# pimc.net
KiCad netlist of a schematic drawn in EAGLE
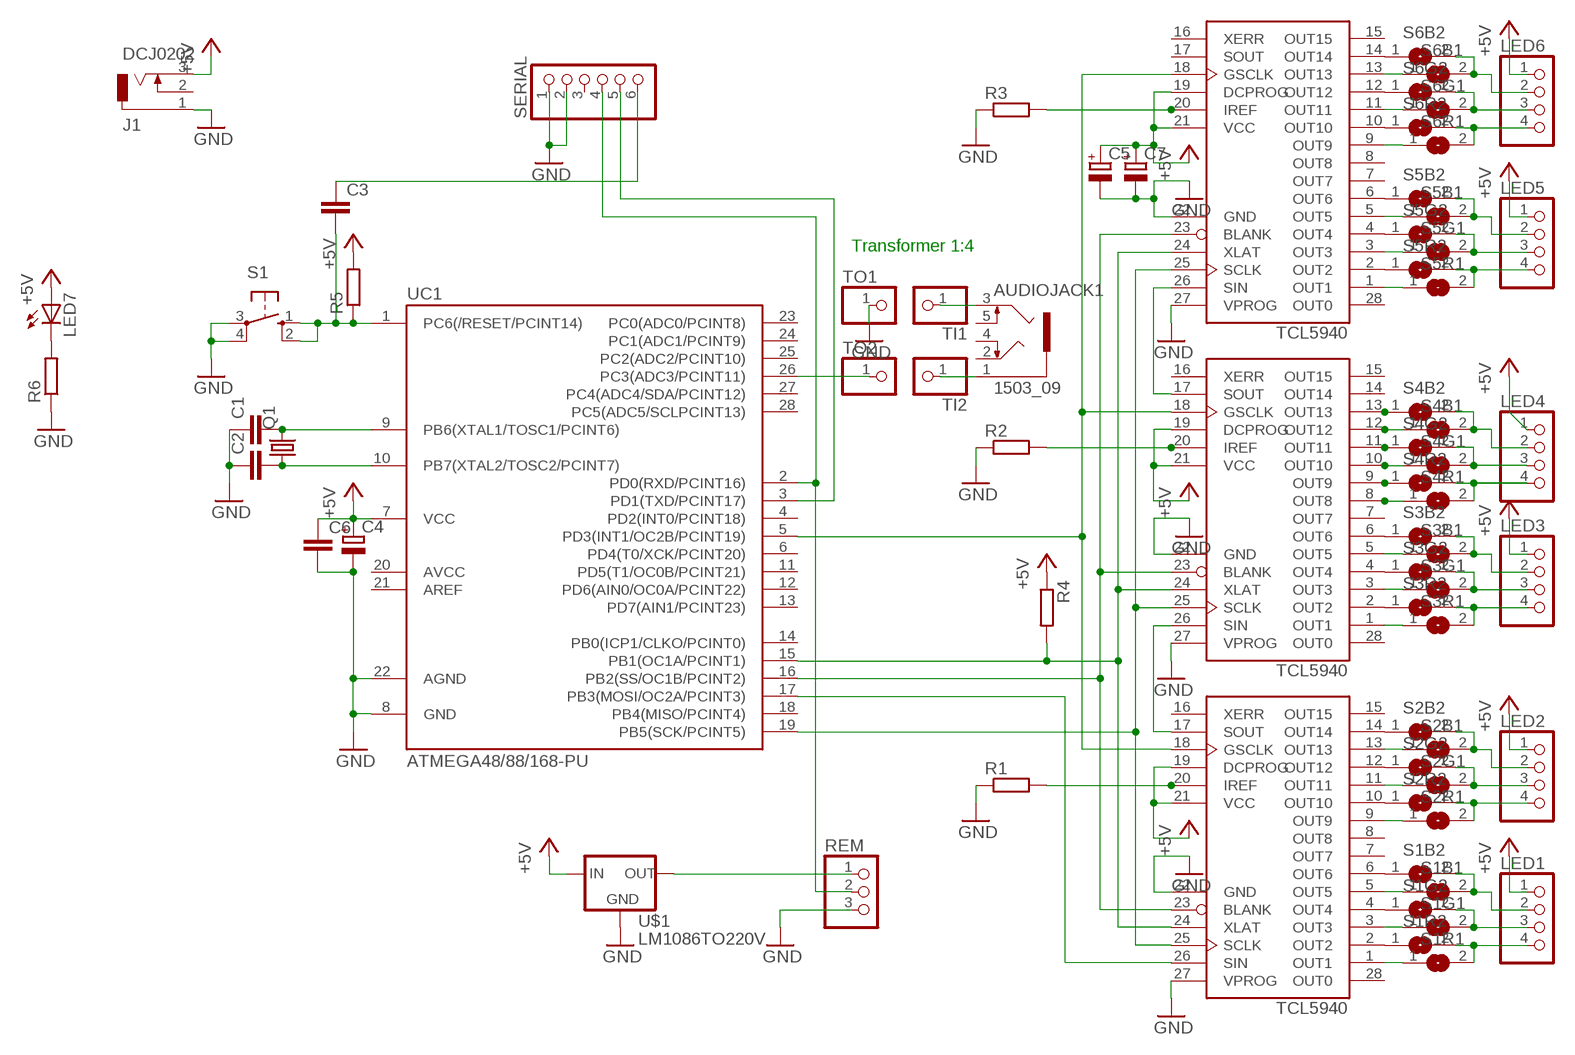
[diagram p0: schematic, sheet 1]

(export (version "E")
  (design (tool "Eeschema 10.0.6"))
  (components
    (comp (ref "AUDIOJACK1")
      (value "1503_09")
      (footprint "eagle-import:1503_09")
      (libsource (lib "eagle-import") (part "1503_09"))
    )
    (comp (ref "C1")
      (value "C-EU025-025X050")
      (footprint "eagle-import:C025-025X050")
      (libsource (lib "eagle-import") (part "C-EU025-025X050"))
    )
    (comp (ref "C2")
      (value "C-EU025-025X050")
      (footprint "eagle-import:C025-025X050")
      (libsource (lib "eagle-import") (part "C-EU025-025X050"))
    )
    (comp (ref "C3")
      (value "C-EU025-025X050")
      (footprint "eagle-import:C025-025X050")
      (libsource (lib "eagle-import") (part "C-EU025-025X050"))
    )
    (comp (ref "C4")
      (value "CPOL-EUE3.5-8")
      (footprint "eagle-import:E3,5-8")
      (libsource (lib "eagle-import") (part "CPOL-EUE3.5-8"))
    )
    (comp (ref "C5")
      (value "CPOL-EUE3.5-8")
      (footprint "eagle-import:E3,5-8")
      (libsource (lib "eagle-import") (part "CPOL-EUE3.5-8"))
    )
    (comp (ref "C6")
      (value "C-EU025-025X050")
      (footprint "eagle-import:C025-025X050")
      (libsource (lib "eagle-import") (part "C-EU025-025X050"))
    )
    (comp (ref "C7")
      (value "CPOL-EUE3.5-8")
      (footprint "eagle-import:E3,5-8")
      (libsource (lib "eagle-import") (part "CPOL-EUE3.5-8"))
    )
    (comp (ref "DRV1")
      (value "TCL5940")
      (footprint "eagle-import:DIP28")
      (libsource (lib "eagle-import") (part "TCL5940"))
    )
    (comp (ref "DRV2")
      (value "TCL5940")
      (footprint "eagle-import:DIP28")
      (libsource (lib "eagle-import") (part "TCL5940"))
    )
    (comp (ref "DRV3")
      (value "TCL5940")
      (footprint "eagle-import:DIP28")
      (libsource (lib "eagle-import") (part "TCL5940"))
    )
    (comp (ref "J1")
      (value "DCJ0202")
      (footprint "eagle-import:DCJ0202")
      (libsource (lib "eagle-import") (part "DCJ0202"))
    )
    (comp (ref "LED1")
      (value "PINHD-1X4")
      (footprint "eagle-import:1X04")
      (libsource (lib "eagle-import") (part "PINHD-1X4"))
    )
    (comp (ref "LED2")
      (value "PINHD-1X4")
      (footprint "eagle-import:1X04")
      (libsource (lib "eagle-import") (part "PINHD-1X4"))
    )
    (comp (ref "LED3")
      (value "PINHD-1X4")
      (footprint "eagle-import:1X04")
      (libsource (lib "eagle-import") (part "PINHD-1X4"))
    )
    (comp (ref "LED4")
      (value "PINHD-1X4")
      (footprint "eagle-import:1X04")
      (libsource (lib "eagle-import") (part "PINHD-1X4"))
    )
    (comp (ref "LED5")
      (value "PINHD-1X4")
      (footprint "eagle-import:1X04")
      (libsource (lib "eagle-import") (part "PINHD-1X4"))
    )
    (comp (ref "LED6")
      (value "PINHD-1X4")
      (footprint "eagle-import:1X04")
      (libsource (lib "eagle-import") (part "PINHD-1X4"))
    )
    (comp (ref "LED7")
      (value "LED5MM")
      (footprint "eagle-import:LED5MM")
      (libsource (lib "eagle-import") (part "LED5MM"))
    )
    (comp (ref "Q1")
      (value "CRYSTALHC49S")
      (footprint "eagle-import:HC49_S")
      (libsource (lib "eagle-import") (part "CRYSTALHC49S"))
    )
    (comp (ref "R1")
      (value "R-EU_0204/7")
      (footprint "eagle-import:0204_7")
      (libsource (lib "eagle-import") (part "R-EU_0204/7"))
    )
    (comp (ref "R2")
      (value "R-EU_0204/7")
      (footprint "eagle-import:0204_7")
      (libsource (lib "eagle-import") (part "R-EU_0204/7"))
    )
    (comp (ref "R3")
      (value "R-EU_0204/7")
      (footprint "eagle-import:0204_7")
      (libsource (lib "eagle-import") (part "R-EU_0204/7"))
    )
    (comp (ref "R4")
      (value "R-EU_0204/7")
      (footprint "eagle-import:0204_7")
      (libsource (lib "eagle-import") (part "R-EU_0204/7"))
    )
    (comp (ref "R5")
      (value "R-EU_0204/7")
      (footprint "eagle-import:0204_7")
      (libsource (lib "eagle-import") (part "R-EU_0204/7"))
    )
    (comp (ref "R6")
      (value "R-EU_0204/7")
      (footprint "eagle-import:0204_7")
      (libsource (lib "eagle-import") (part "R-EU_0204/7"))
    )
    (comp (ref "REM")
      (value "PINHD-1X3")
      (footprint "eagle-import:1X03")
      (libsource (lib "eagle-import") (part "PINHD-1X3"))
    )
    (comp (ref "S1")
      (value "10-XX")
      (footprint "eagle-import:B3F-10XX")
      (fields (field (name "MPN") "B3F-1000"))
      (libsource (lib "eagle-import") (part "10-XX"))
    )
    (comp (ref "S1B1")
      (value "SJ")
      (footprint "eagle-import:SJ")
      (libsource (lib "eagle-import") (part "SJ"))
    )
    (comp (ref "S1B2")
      (value "SJ")
      (footprint "eagle-import:SJ")
      (libsource (lib "eagle-import") (part "SJ"))
    )
    (comp (ref "S1G1")
      (value "SJ")
      (footprint "eagle-import:SJ")
      (libsource (lib "eagle-import") (part "SJ"))
    )
    (comp (ref "S1G2")
      (value "SJ")
      (footprint "eagle-import:SJ")
      (libsource (lib "eagle-import") (part "SJ"))
    )
    (comp (ref "S1R1")
      (value "SJ")
      (footprint "eagle-import:SJ")
      (libsource (lib "eagle-import") (part "SJ"))
    )
    (comp (ref "S1R2")
      (value "SJ")
      (footprint "eagle-import:SJ")
      (libsource (lib "eagle-import") (part "SJ"))
    )
    (comp (ref "S2B1")
      (value "SJ")
      (footprint "eagle-import:SJ")
      (libsource (lib "eagle-import") (part "SJ"))
    )
    (comp (ref "S2B2")
      (value "SJ")
      (footprint "eagle-import:SJ")
      (libsource (lib "eagle-import") (part "SJ"))
    )
    (comp (ref "S2G1")
      (value "SJ")
      (footprint "eagle-import:SJ")
      (libsource (lib "eagle-import") (part "SJ"))
    )
    (comp (ref "S2G2")
      (value "SJ")
      (footprint "eagle-import:SJ")
      (libsource (lib "eagle-import") (part "SJ"))
    )
    (comp (ref "S2R1")
      (value "SJ")
      (footprint "eagle-import:SJ")
      (libsource (lib "eagle-import") (part "SJ"))
    )
    (comp (ref "S2R2")
      (value "SJ")
      (footprint "eagle-import:SJ")
      (libsource (lib "eagle-import") (part "SJ"))
    )
    (comp (ref "S3B1")
      (value "SJ")
      (footprint "eagle-import:SJ")
      (libsource (lib "eagle-import") (part "SJ"))
    )
    (comp (ref "S3B2")
      (value "SJ")
      (footprint "eagle-import:SJ")
      (libsource (lib "eagle-import") (part "SJ"))
    )
    (comp (ref "S3G1")
      (value "SJ")
      (footprint "eagle-import:SJ")
      (libsource (lib "eagle-import") (part "SJ"))
    )
    (comp (ref "S3G2")
      (value "SJ")
      (footprint "eagle-import:SJ")
      (libsource (lib "eagle-import") (part "SJ"))
    )
    (comp (ref "S3R1")
      (value "SJ")
      (footprint "eagle-import:SJ")
      (libsource (lib "eagle-import") (part "SJ"))
    )
    (comp (ref "S3R2")
      (value "SJ")
      (footprint "eagle-import:SJ")
      (libsource (lib "eagle-import") (part "SJ"))
    )
    (comp (ref "S4B1")
      (value "SJ")
      (footprint "eagle-import:SJ")
      (libsource (lib "eagle-import") (part "SJ"))
    )
    (comp (ref "S4B2")
      (value "SJ")
      (footprint "eagle-import:SJ")
      (libsource (lib "eagle-import") (part "SJ"))
    )
    (comp (ref "S4G1")
      (value "SJ")
      (footprint "eagle-import:SJ")
      (libsource (lib "eagle-import") (part "SJ"))
    )
    (comp (ref "S4G2")
      (value "SJ")
      (footprint "eagle-import:SJ")
      (libsource (lib "eagle-import") (part "SJ"))
    )
    (comp (ref "S4R1")
      (value "SJ")
      (footprint "eagle-import:SJ")
      (libsource (lib "eagle-import") (part "SJ"))
    )
    (comp (ref "S4R2")
      (value "SJ")
      (footprint "eagle-import:SJ")
      (libsource (lib "eagle-import") (part "SJ"))
    )
    (comp (ref "S5B1")
      (value "SJ")
      (footprint "eagle-import:SJ")
      (libsource (lib "eagle-import") (part "SJ"))
    )
    (comp (ref "S5B2")
      (value "SJ")
      (footprint "eagle-import:SJ")
      (libsource (lib "eagle-import") (part "SJ"))
    )
    (comp (ref "S5G1")
      (value "SJ")
      (footprint "eagle-import:SJ")
      (libsource (lib "eagle-import") (part "SJ"))
    )
    (comp (ref "S5G2")
      (value "SJ")
      (footprint "eagle-import:SJ")
      (libsource (lib "eagle-import") (part "SJ"))
    )
    (comp (ref "S5R1")
      (value "SJ")
      (footprint "eagle-import:SJ")
      (libsource (lib "eagle-import") (part "SJ"))
    )
    (comp (ref "S5R2")
      (value "SJ")
      (footprint "eagle-import:SJ")
      (libsource (lib "eagle-import") (part "SJ"))
    )
    (comp (ref "S6B1")
      (value "SJ")
      (footprint "eagle-import:SJ")
      (libsource (lib "eagle-import") (part "SJ"))
    )
    (comp (ref "S6B2")
      (value "SJ")
      (footprint "eagle-import:SJ")
      (libsource (lib "eagle-import") (part "SJ"))
    )
    (comp (ref "S6G1")
      (value "SJ")
      (footprint "eagle-import:SJ")
      (libsource (lib "eagle-import") (part "SJ"))
    )
    (comp (ref "S6G2")
      (value "SJ")
      (footprint "eagle-import:SJ")
      (libsource (lib "eagle-import") (part "SJ"))
    )
    (comp (ref "S6R1")
      (value "SJ")
      (footprint "eagle-import:SJ")
      (libsource (lib "eagle-import") (part "SJ"))
    )
    (comp (ref "S6R2")
      (value "SJ")
      (footprint "eagle-import:SJ")
      (libsource (lib "eagle-import") (part "SJ"))
    )
    (comp (ref "SERIAL")
      (value "PINHD-1X6")
      (footprint "eagle-import:1X06")
      (libsource (lib "eagle-import") (part "PINHD-1X6"))
    )
    (comp (ref "TI1")
      (value "PINHD-1X1")
      (footprint "eagle-import:1X01")
      (libsource (lib "eagle-import") (part "PINHD-1X1"))
    )
    (comp (ref "TI2")
      (value "PINHD-1X1")
      (footprint "eagle-import:1X01")
      (libsource (lib "eagle-import") (part "PINHD-1X1"))
    )
    (comp (ref "TO1")
      (value "PINHD-1X1")
      (footprint "eagle-import:1X01")
      (libsource (lib "eagle-import") (part "PINHD-1X1"))
    )
    (comp (ref "TO2")
      (value "PINHD-1X1")
      (footprint "eagle-import:1X01")
      (libsource (lib "eagle-import") (part "PINHD-1X1"))
    )
    (comp (ref "U$1")
      (value "LM1086TO220V")
      (footprint "eagle-import:TO220S")
      (libsource (lib "eagle-import") (part "LM1086TO220V"))
    )
    (comp (ref "UC1")
      (value "ATMEGA48/88/168-PU")
      (footprint "eagle-import:DIL28-3")
      (libsource (lib "eagle-import") (part "ATMEGA48/88/168-PU"))
    )
  )
  (nets
    (net (code "1") (name "+5V") (class "Default")
      (node (ref "C4") (pin "+") (pinfunction "+_+") (pintype "passive"))
      (node (ref "C5") (pin "+") (pinfunction "+_+") (pintype "passive"))
      (node (ref "C6") (pin "1") (pinfunction "1_1") (pintype "passive"))
      (node (ref "C7") (pin "+") (pinfunction "+_+") (pintype "passive"))
      (node (ref "DRV1") (pin "19") (pinfunction "DCPROG_19") (pintype "input"))
      (node (ref "DRV1") (pin "21") (pinfunction "VCC_21") (pintype "power_in"))
      (node (ref "DRV2") (pin "19") (pinfunction "DCPROG_19") (pintype "input"))
      (node (ref "DRV2") (pin "21") (pinfunction "VCC_21") (pintype "power_in"))
      (node (ref "DRV3") (pin "19") (pinfunction "DCPROG_19") (pintype "input"))
      (node (ref "DRV3") (pin "21") (pinfunction "VCC_21") (pintype "power_in"))
      (node (ref "J1") (pin "3") (pinfunction "3_3") (pintype "passive"))
      (node (ref "LED1") (pin "1") (pinfunction "1_1") (pintype "passive"))
      (node (ref "LED2") (pin "1") (pinfunction "1_1") (pintype "passive"))
      (node (ref "LED3") (pin "1") (pinfunction "1_1") (pintype "passive"))
      (node (ref "LED4") (pin "1") (pinfunction "1_1") (pintype "passive"))
      (node (ref "LED5") (pin "1") (pinfunction "1_1") (pintype "passive"))
      (node (ref "LED6") (pin "1") (pinfunction "1_1") (pintype "passive"))
      (node (ref "LED7") (pin "A") (pinfunction "A_A") (pintype "passive"))
      (node (ref "R4") (pin "1") (pinfunction "1_1") (pintype "passive"))
      (node (ref "R5") (pin "2") (pinfunction "2_2") (pintype "passive"))
      (node (ref "U$1") (pin "3") (pinfunction "IN_3") (pintype "input"))
      (node (ref "UC1") (pin "7") (pinfunction "VCC_7") (pintype "power_in"))
    )
    (net (code "2") (name "GND") (class "Default")
      (node (ref "C1") (pin "1") (pinfunction "1_1") (pintype "passive"))
      (node (ref "C2") (pin "1") (pinfunction "1_1") (pintype "passive"))
      (node (ref "C4") (pin "-") (pinfunction "-_-") (pintype "passive"))
      (node (ref "C5") (pin "-") (pinfunction "-_-") (pintype "passive"))
      (node (ref "C6") (pin "2") (pinfunction "2_2") (pintype "passive"))
      (node (ref "C7") (pin "-") (pinfunction "-_-") (pintype "passive"))
      (node (ref "DRV1") (pin "22") (pinfunction "GND_22") (pintype "power_in"))
      (node (ref "DRV1") (pin "27") (pinfunction "VPROG_27") (pintype "bidirectional"))
      (node (ref "DRV2") (pin "22") (pinfunction "GND_22") (pintype "power_in"))
      (node (ref "DRV2") (pin "27") (pinfunction "VPROG_27") (pintype "bidirectional"))
      (node (ref "DRV3") (pin "22") (pinfunction "GND_22") (pintype "power_in"))
      (node (ref "DRV3") (pin "27") (pinfunction "VPROG_27") (pintype "bidirectional"))
      (node (ref "J1") (pin "1") (pinfunction "1_1") (pintype "passive"))
      (node (ref "R1") (pin "1") (pinfunction "1_1") (pintype "passive"))
      (node (ref "R2") (pin "1") (pinfunction "1_1") (pintype "passive"))
      (node (ref "R3") (pin "1") (pinfunction "1_1") (pintype "passive"))
      (node (ref "R6") (pin "1") (pinfunction "1_1") (pintype "passive"))
      (node (ref "REM") (pin "3") (pinfunction "3_3") (pintype "passive"))
      (node (ref "S1") (pin "3") (pinfunction "P_3") (pintype "passive"))
      (node (ref "S1") (pin "4") (pinfunction "P1_4") (pintype "passive"))
      (node (ref "SERIAL") (pin "1") (pinfunction "1_1") (pintype "passive"))
      (node (ref "SERIAL") (pin "2") (pinfunction "2_2") (pintype "passive"))
      (node (ref "TO1") (pin "1") (pinfunction "1_1") (pintype "passive"))
      (node (ref "U$1") (pin "1") (pinfunction "GND_1") (pintype "input"))
      (node (ref "UC1") (pin "22") (pinfunction "AGND_22") (pintype "power_in"))
      (node (ref "UC1") (pin "8") (pinfunction "GND_8") (pintype "power_in"))
    )
    (net (code "3") (name "Net-(AUDIOJACK1-Pad1)") (class "Default")
      (node (ref "AUDIOJACK1") (pin "1") (pinfunction "1_1") (pintype "passive"))
      (node (ref "TI2") (pin "1") (pinfunction "1_1") (pintype "passive"))
    )
    (net (code "4") (name "Net-(AUDIOJACK1-Pad3)") (class "Default")
      (node (ref "AUDIOJACK1") (pin "3") (pinfunction "3_3") (pintype "passive"))
      (node (ref "TI1") (pin "1") (pinfunction "1_1") (pintype "passive"))
    )
    (net (code "5") (name "Net-(C3-Pad1)") (class "Default")
      (node (ref "C3") (pin "1") (pinfunction "1_1") (pintype "passive"))
      (node (ref "SERIAL") (pin "6") (pinfunction "6_6") (pintype "passive"))
    )
    (net (code "6") (name "Net-(DRV1-BLANK)") (class "Default")
      (node (ref "DRV1") (pin "23") (pinfunction "BLANK_23") (pintype "input"))
      (node (ref "DRV2") (pin "23") (pinfunction "BLANK_23") (pintype "input"))
      (node (ref "DRV3") (pin "23") (pinfunction "BLANK_23") (pintype "input"))
      (node (ref "UC1") (pin "16") (pinfunction "PB2(SS/OC1B/PCINT2)_16") (pintype "bidirectional"))
    )
    (net (code "7") (name "Net-(DRV1-GSCLK)") (class "Default")
      (node (ref "DRV1") (pin "18") (pinfunction "GSCLK_18") (pintype "input"))
      (node (ref "DRV2") (pin "18") (pinfunction "GSCLK_18") (pintype "input"))
      (node (ref "DRV3") (pin "18") (pinfunction "GSCLK_18") (pintype "input"))
      (node (ref "UC1") (pin "5") (pinfunction "PD3(INT1/OC2B/PCINT19)_5") (pintype "bidirectional"))
    )
    (net (code "8") (name "Net-(DRV1-IREF)") (class "Default")
      (node (ref "DRV1") (pin "20") (pinfunction "IREF_20") (pintype "input"))
      (node (ref "R1") (pin "2") (pinfunction "2_2") (pintype "passive"))
    )
    (net (code "9") (name "Net-(DRV1-OUT1)") (class "Default")
      (node (ref "DRV1") (pin "1") (pinfunction "OUT1_1") (pintype "output"))
      (node (ref "S1R1") (pin "1") (pinfunction "1_1") (pintype "passive"))
    )
    (net (code "10") (name "Net-(DRV1-OUT2)") (class "Default")
      (node (ref "DRV1") (pin "2") (pinfunction "OUT2_2") (pintype "output"))
      (node (ref "S1R2") (pin "1") (pinfunction "1_1") (pintype "passive"))
    )
    (net (code "11") (name "Net-(DRV1-OUT3)") (class "Default")
      (node (ref "DRV1") (pin "3") (pinfunction "OUT3_3") (pintype "output"))
      (node (ref "S1G1") (pin "1") (pinfunction "1_1") (pintype "passive"))
    )
    (net (code "12") (name "Net-(DRV1-OUT4)") (class "Default")
      (node (ref "DRV1") (pin "4") (pinfunction "OUT4_4") (pintype "output"))
      (node (ref "S1G2") (pin "1") (pinfunction "1_1") (pintype "passive"))
    )
    (net (code "13") (name "Net-(DRV1-OUT5)") (class "Default")
      (node (ref "DRV1") (pin "5") (pinfunction "OUT5_5") (pintype "output"))
      (node (ref "S1B1") (pin "1") (pinfunction "1_1") (pintype "passive"))
    )
    (net (code "14") (name "Net-(DRV1-OUT6)") (class "Default")
      (node (ref "DRV1") (pin "6") (pinfunction "OUT6_6") (pintype "output"))
      (node (ref "S1B2") (pin "1") (pinfunction "1_1") (pintype "passive"))
    )
    (net (code "15") (name "Net-(DRV1-OUT9)") (class "Default")
      (node (ref "DRV1") (pin "9") (pinfunction "OUT9_9") (pintype "output"))
      (node (ref "S2R1") (pin "1") (pinfunction "1_1") (pintype "passive"))
    )
    (net (code "16") (name "Net-(DRV1-OUT10)") (class "Default")
      (node (ref "DRV1") (pin "10") (pinfunction "OUT10_10") (pintype "output"))
      (node (ref "S2R2") (pin "1") (pinfunction "1_1") (pintype "passive"))
    )
    (net (code "17") (name "Net-(DRV1-OUT11)") (class "Default")
      (node (ref "DRV1") (pin "11") (pinfunction "OUT11_11") (pintype "output"))
      (node (ref "S2G1") (pin "1") (pinfunction "1_1") (pintype "passive"))
    )
    (net (code "18") (name "Net-(DRV1-OUT12)") (class "Default")
      (node (ref "DRV1") (pin "12") (pinfunction "OUT12_12") (pintype "output"))
      (node (ref "S2G2") (pin "1") (pinfunction "1_1") (pintype "passive"))
    )
    (net (code "19") (name "Net-(DRV1-OUT13)") (class "Default")
      (node (ref "DRV1") (pin "13") (pinfunction "OUT13_13") (pintype "output"))
      (node (ref "S2B1") (pin "1") (pinfunction "1_1") (pintype "passive"))
    )
    (net (code "20") (name "Net-(DRV1-OUT14)") (class "Default")
      (node (ref "DRV1") (pin "14") (pinfunction "OUT14_14") (pintype "output"))
      (node (ref "S2B2") (pin "1") (pinfunction "1_1") (pintype "passive"))
    )
    (net (code "21") (name "Net-(DRV1-SCLK)") (class "Default")
      (node (ref "DRV1") (pin "25") (pinfunction "SCLK_25") (pintype "input"))
      (node (ref "DRV2") (pin "25") (pinfunction "SCLK_25") (pintype "input"))
      (node (ref "DRV3") (pin "25") (pinfunction "SCLK_25") (pintype "input"))
      (node (ref "UC1") (pin "19") (pinfunction "PB5(SCK/PCINT5)_19") (pintype "bidirectional"))
    )
    (net (code "22") (name "Net-(DRV1-SIN)") (class "Default")
      (node (ref "DRV1") (pin "26") (pinfunction "SIN_26") (pintype "input"))
      (node (ref "UC1") (pin "17") (pinfunction "PB3(MOSI/OC2A/PCINT3)_17") (pintype "bidirectional"))
    )
    (net (code "23") (name "Net-(DRV1-SOUT)") (class "Default")
      (node (ref "DRV1") (pin "17") (pinfunction "SOUT_17") (pintype "output"))
      (node (ref "DRV2") (pin "26") (pinfunction "SIN_26") (pintype "input"))
    )
    (net (code "24") (name "Net-(DRV1-XLAT)") (class "Default")
      (node (ref "DRV1") (pin "24") (pinfunction "XLAT_24") (pintype "input"))
      (node (ref "DRV2") (pin "24") (pinfunction "XLAT_24") (pintype "input"))
      (node (ref "DRV3") (pin "24") (pinfunction "XLAT_24") (pintype "input"))
      (node (ref "R4") (pin "2") (pinfunction "2_2") (pintype "passive"))
      (node (ref "UC1") (pin "15") (pinfunction "PB1(OC1A/PCINT1)_15") (pintype "bidirectional"))
    )
    (net (code "25") (name "Net-(DRV2-IREF)") (class "Default")
      (node (ref "DRV2") (pin "20") (pinfunction "IREF_20") (pintype "input"))
      (node (ref "R2") (pin "2") (pinfunction "2_2") (pintype "passive"))
    )
    (net (code "26") (name "Net-(DRV2-OUT1)") (class "Default")
      (node (ref "DRV2") (pin "1") (pinfunction "OUT1_1") (pintype "output"))
      (node (ref "S3R1") (pin "1") (pinfunction "1_1") (pintype "passive"))
    )
    (net (code "27") (name "Net-(DRV2-OUT2)") (class "Default")
      (node (ref "DRV2") (pin "2") (pinfunction "OUT2_2") (pintype "output"))
      (node (ref "S3R2") (pin "1") (pinfunction "1_1") (pintype "passive"))
    )
    (net (code "28") (name "Net-(DRV2-OUT3)") (class "Default")
      (node (ref "DRV2") (pin "3") (pinfunction "OUT3_3") (pintype "output"))
      (node (ref "S3G1") (pin "1") (pinfunction "1_1") (pintype "passive"))
    )
    (net (code "29") (name "Net-(DRV2-OUT4)") (class "Default")
      (node (ref "DRV2") (pin "4") (pinfunction "OUT4_4") (pintype "output"))
      (node (ref "S3G2") (pin "1") (pinfunction "1_1") (pintype "passive"))
    )
    (net (code "30") (name "Net-(DRV2-OUT5)") (class "Default")
      (node (ref "DRV2") (pin "5") (pinfunction "OUT5_5") (pintype "output"))
      (node (ref "S3B1") (pin "1") (pinfunction "1_1") (pintype "passive"))
    )
    (net (code "31") (name "Net-(DRV2-OUT6)") (class "Default")
      (node (ref "DRV2") (pin "6") (pinfunction "OUT6_6") (pintype "output"))
      (node (ref "S3B2") (pin "1") (pinfunction "1_1") (pintype "passive"))
    )
    (net (code "32") (name "Net-(DRV2-OUT8)") (class "Default")
      (node (ref "DRV2") (pin "8") (pinfunction "OUT8_8") (pintype "output"))
      (node (ref "S4R1") (pin "1") (pinfunction "1_1") (pintype "passive"))
    )
    (net (code "33") (name "Net-(DRV2-OUT9)") (class "Default")
      (node (ref "DRV2") (pin "9") (pinfunction "OUT9_9") (pintype "output"))
      (node (ref "S4R2") (pin "1") (pinfunction "1_1") (pintype "passive"))
    )
    (net (code "34") (name "Net-(DRV2-OUT10)") (class "Default")
      (node (ref "DRV2") (pin "10") (pinfunction "OUT10_10") (pintype "output"))
      (node (ref "S4G1") (pin "1") (pinfunction "1_1") (pintype "passive"))
    )
    (net (code "35") (name "Net-(DRV2-OUT11)") (class "Default")
      (node (ref "DRV2") (pin "11") (pinfunction "OUT11_11") (pintype "output"))
      (node (ref "S4G2") (pin "1") (pinfunction "1_1") (pintype "passive"))
    )
    (net (code "36") (name "Net-(DRV2-OUT12)") (class "Default")
      (node (ref "DRV2") (pin "12") (pinfunction "OUT12_12") (pintype "output"))
      (node (ref "S4B1") (pin "1") (pinfunction "1_1") (pintype "passive"))
    )
    (net (code "37") (name "Net-(DRV2-OUT13)") (class "Default")
      (node (ref "DRV2") (pin "13") (pinfunction "OUT13_13") (pintype "output"))
      (node (ref "S4B2") (pin "1") (pinfunction "1_1") (pintype "passive"))
    )
    (net (code "38") (name "Net-(DRV2-SOUT)") (class "Default")
      (node (ref "DRV2") (pin "17") (pinfunction "SOUT_17") (pintype "output"))
      (node (ref "DRV3") (pin "26") (pinfunction "SIN_26") (pintype "input"))
    )
    (net (code "39") (name "Net-(DRV3-IREF)") (class "Default")
      (node (ref "DRV3") (pin "20") (pinfunction "IREF_20") (pintype "input"))
      (node (ref "R3") (pin "2") (pinfunction "2_2") (pintype "passive"))
    )
    (net (code "40") (name "Net-(DRV3-OUT1)") (class "Default")
      (node (ref "DRV3") (pin "1") (pinfunction "OUT1_1") (pintype "output"))
      (node (ref "S5R1") (pin "1") (pinfunction "1_1") (pintype "passive"))
    )
    (net (code "41") (name "Net-(DRV3-OUT2)") (class "Default")
      (node (ref "DRV3") (pin "2") (pinfunction "OUT2_2") (pintype "output"))
      (node (ref "S5R2") (pin "1") (pinfunction "1_1") (pintype "passive"))
    )
    (net (code "42") (name "Net-(DRV3-OUT3)") (class "Default")
      (node (ref "DRV3") (pin "3") (pinfunction "OUT3_3") (pintype "output"))
      (node (ref "S5G1") (pin "1") (pinfunction "1_1") (pintype "passive"))
    )
    (net (code "43") (name "Net-(DRV3-OUT4)") (class "Default")
      (node (ref "DRV3") (pin "4") (pinfunction "OUT4_4") (pintype "output"))
      (node (ref "S5G2") (pin "1") (pinfunction "1_1") (pintype "passive"))
    )
    (net (code "44") (name "Net-(DRV3-OUT5)") (class "Default")
      (node (ref "DRV3") (pin "5") (pinfunction "OUT5_5") (pintype "output"))
      (node (ref "S5B1") (pin "1") (pinfunction "1_1") (pintype "passive"))
    )
    (net (code "45") (name "Net-(DRV3-OUT6)") (class "Default")
      (node (ref "DRV3") (pin "6") (pinfunction "OUT6_6") (pintype "output"))
      (node (ref "S5B2") (pin "1") (pinfunction "1_1") (pintype "passive"))
    )
    (net (code "46") (name "Net-(DRV3-OUT9)") (class "Default")
      (node (ref "DRV3") (pin "9") (pinfunction "OUT9_9") (pintype "output"))
      (node (ref "S6R1") (pin "1") (pinfunction "1_1") (pintype "passive"))
    )
    (net (code "47") (name "Net-(DRV3-OUT10)") (class "Default")
      (node (ref "DRV3") (pin "10") (pinfunction "OUT10_10") (pintype "output"))
      (node (ref "S6R2") (pin "1") (pinfunction "1_1") (pintype "passive"))
    )
    (net (code "48") (name "Net-(DRV3-OUT11)") (class "Default")
      (node (ref "DRV3") (pin "11") (pinfunction "OUT11_11") (pintype "output"))
      (node (ref "S6G1") (pin "1") (pinfunction "1_1") (pintype "passive"))
    )
    (net (code "49") (name "Net-(DRV3-OUT12)") (class "Default")
      (node (ref "DRV3") (pin "12") (pinfunction "OUT12_12") (pintype "output"))
      (node (ref "S6G2") (pin "1") (pinfunction "1_1") (pintype "passive"))
    )
    (net (code "50") (name "Net-(DRV3-OUT13)") (class "Default")
      (node (ref "DRV3") (pin "13") (pinfunction "OUT13_13") (pintype "output"))
      (node (ref "S6B1") (pin "1") (pinfunction "1_1") (pintype "passive"))
    )
    (net (code "51") (name "Net-(DRV3-OUT14)") (class "Default")
      (node (ref "DRV3") (pin "14") (pinfunction "OUT14_14") (pintype "output"))
      (node (ref "S6B2") (pin "1") (pinfunction "1_1") (pintype "passive"))
    )
    (net (code "52") (name "Net-(LED1-Pad2)") (class "Default")
      (node (ref "LED1") (pin "2") (pinfunction "2_2") (pintype "passive"))
      (node (ref "S1B1") (pin "2") (pinfunction "2_2") (pintype "passive"))
      (node (ref "S1B2") (pin "2") (pinfunction "2_2") (pintype "passive"))
    )
    (net (code "53") (name "Net-(LED1-Pad3)") (class "Default")
      (node (ref "LED1") (pin "3") (pinfunction "3_3") (pintype "passive"))
      (node (ref "S1G1") (pin "2") (pinfunction "2_2") (pintype "passive"))
      (node (ref "S1G2") (pin "2") (pinfunction "2_2") (pintype "passive"))
    )
    (net (code "54") (name "Net-(LED1-Pad4)") (class "Default")
      (node (ref "LED1") (pin "4") (pinfunction "4_4") (pintype "passive"))
      (node (ref "S1R1") (pin "2") (pinfunction "2_2") (pintype "passive"))
      (node (ref "S1R2") (pin "2") (pinfunction "2_2") (pintype "passive"))
    )
    (net (code "55") (name "Net-(LED2-Pad2)") (class "Default")
      (node (ref "LED2") (pin "2") (pinfunction "2_2") (pintype "passive"))
      (node (ref "S2B1") (pin "2") (pinfunction "2_2") (pintype "passive"))
      (node (ref "S2B2") (pin "2") (pinfunction "2_2") (pintype "passive"))
    )
    (net (code "56") (name "Net-(LED2-Pad3)") (class "Default")
      (node (ref "LED2") (pin "3") (pinfunction "3_3") (pintype "passive"))
      (node (ref "S2G1") (pin "2") (pinfunction "2_2") (pintype "passive"))
      (node (ref "S2G2") (pin "2") (pinfunction "2_2") (pintype "passive"))
    )
    (net (code "57") (name "Net-(LED2-Pad4)") (class "Default")
      (node (ref "LED2") (pin "4") (pinfunction "4_4") (pintype "passive"))
      (node (ref "S2R1") (pin "2") (pinfunction "2_2") (pintype "passive"))
      (node (ref "S2R2") (pin "2") (pinfunction "2_2") (pintype "passive"))
    )
    (net (code "58") (name "Net-(LED3-Pad2)") (class "Default")
      (node (ref "LED3") (pin "2") (pinfunction "2_2") (pintype "passive"))
      (node (ref "S3B1") (pin "2") (pinfunction "2_2") (pintype "passive"))
      (node (ref "S3B2") (pin "2") (pinfunction "2_2") (pintype "passive"))
    )
    (net (code "59") (name "Net-(LED3-Pad3)") (class "Default")
      (node (ref "LED3") (pin "3") (pinfunction "3_3") (pintype "passive"))
      (node (ref "S3G1") (pin "2") (pinfunction "2_2") (pintype "passive"))
      (node (ref "S3G2") (pin "2") (pinfunction "2_2") (pintype "passive"))
    )
    (net (code "60") (name "Net-(LED3-Pad4)") (class "Default")
      (node (ref "LED3") (pin "4") (pinfunction "4_4") (pintype "passive"))
      (node (ref "S3R1") (pin "2") (pinfunction "2_2") (pintype "passive"))
      (node (ref "S3R2") (pin "2") (pinfunction "2_2") (pintype "passive"))
    )
    (net (code "61") (name "Net-(LED4-Pad2)") (class "Default")
      (node (ref "LED4") (pin "2") (pinfunction "2_2") (pintype "passive"))
      (node (ref "S4B1") (pin "2") (pinfunction "2_2") (pintype "passive"))
      (node (ref "S4B2") (pin "2") (pinfunction "2_2") (pintype "passive"))
    )
    (net (code "62") (name "Net-(LED4-Pad3)") (class "Default")
      (node (ref "LED4") (pin "3") (pinfunction "3_3") (pintype "passive"))
      (node (ref "S4G1") (pin "2") (pinfunction "2_2") (pintype "passive"))
      (node (ref "S4G2") (pin "2") (pinfunction "2_2") (pintype "passive"))
    )
    (net (code "63") (name "Net-(LED4-Pad4)") (class "Default")
      (node (ref "LED4") (pin "4") (pinfunction "4_4") (pintype "passive"))
      (node (ref "S4R1") (pin "2") (pinfunction "2_2") (pintype "passive"))
      (node (ref "S4R2") (pin "2") (pinfunction "2_2") (pintype "passive"))
    )
    (net (code "64") (name "Net-(LED5-Pad2)") (class "Default")
      (node (ref "LED5") (pin "2") (pinfunction "2_2") (pintype "passive"))
      (node (ref "S5B1") (pin "2") (pinfunction "2_2") (pintype "passive"))
      (node (ref "S5B2") (pin "2") (pinfunction "2_2") (pintype "passive"))
    )
    (net (code "65") (name "Net-(LED5-Pad3)") (class "Default")
      (node (ref "LED5") (pin "3") (pinfunction "3_3") (pintype "passive"))
      (node (ref "S5G1") (pin "2") (pinfunction "2_2") (pintype "passive"))
      (node (ref "S5G2") (pin "2") (pinfunction "2_2") (pintype "passive"))
    )
    (net (code "66") (name "Net-(LED5-Pad4)") (class "Default")
      (node (ref "LED5") (pin "4") (pinfunction "4_4") (pintype "passive"))
      (node (ref "S5R1") (pin "2") (pinfunction "2_2") (pintype "passive"))
      (node (ref "S5R2") (pin "2") (pinfunction "2_2") (pintype "passive"))
    )
    (net (code "67") (name "Net-(LED6-Pad2)") (class "Default")
      (node (ref "LED6") (pin "2") (pinfunction "2_2") (pintype "passive"))
      (node (ref "S6B1") (pin "2") (pinfunction "2_2") (pintype "passive"))
      (node (ref "S6B2") (pin "2") (pinfunction "2_2") (pintype "passive"))
    )
    (net (code "68") (name "Net-(LED6-Pad3)") (class "Default")
      (node (ref "LED6") (pin "3") (pinfunction "3_3") (pintype "passive"))
      (node (ref "S6G1") (pin "2") (pinfunction "2_2") (pintype "passive"))
      (node (ref "S6G2") (pin "2") (pinfunction "2_2") (pintype "passive"))
    )
    (net (code "69") (name "Net-(LED6-Pad4)") (class "Default")
      (node (ref "LED6") (pin "4") (pinfunction "4_4") (pintype "passive"))
      (node (ref "S6R1") (pin "2") (pinfunction "2_2") (pintype "passive"))
      (node (ref "S6R2") (pin "2") (pinfunction "2_2") (pintype "passive"))
    )
    (net (code "70") (name "Net-(LED7-C)") (class "Default")
      (node (ref "LED7") (pin "K") (pinfunction "C_K") (pintype "passive"))
      (node (ref "R6") (pin "2") (pinfunction "2_2") (pintype "passive"))
    )
    (net (code "71") (name "Net-(S1-S)") (class "Default")
      (node (ref "C3") (pin "2") (pinfunction "2_2") (pintype "passive"))
      (node (ref "R5") (pin "1") (pinfunction "1_1") (pintype "passive"))
      (node (ref "S1") (pin "1") (pinfunction "S_1") (pintype "passive"))
      (node (ref "S1") (pin "2") (pinfunction "S1_2") (pintype "passive"))
      (node (ref "UC1") (pin "1") (pinfunction "PC6(/RESET/PCINT14)_1") (pintype "bidirectional"))
    )
    (net (code "72") (name "Net-(U$1-OUT)") (class "Default")
      (node (ref "REM") (pin "1") (pinfunction "1_1") (pintype "passive"))
      (node (ref "U$1") (pin "2") (pinfunction "OUT_2") (pintype "passive"))
    )
    (net (code "73") (name "Net-(UC1-PB6(XTAL1{slash}TOSC1{slash}PCINT6))") (class "Default")
      (node (ref "C1") (pin "2") (pinfunction "2_2") (pintype "passive"))
      (node (ref "Q1") (pin "2") (pinfunction "2_2") (pintype "passive"))
      (node (ref "UC1") (pin "9") (pinfunction "PB6(XTAL1/TOSC1/PCINT6)_9") (pintype "bidirectional"))
    )
    (net (code "74") (name "Net-(UC1-PB7(XTAL2{slash}TOSC2{slash}PCINT7))") (class "Default")
      (node (ref "C2") (pin "2") (pinfunction "2_2") (pintype "passive"))
      (node (ref "Q1") (pin "1") (pinfunction "1_1") (pintype "passive"))
      (node (ref "UC1") (pin "10") (pinfunction "PB7(XTAL2/TOSC2/PCINT7)_10") (pintype "bidirectional"))
    )
    (net (code "75") (name "Net-(UC1-PC3(ADC3{slash}PCINT11))") (class "Default")
      (node (ref "TO2") (pin "1") (pinfunction "1_1") (pintype "passive"))
      (node (ref "UC1") (pin "26") (pinfunction "PC3(ADC3/PCINT11)_26") (pintype "bidirectional"))
    )
    (net (code "76") (name "Net-(UC1-PD0(RXD{slash}PCINT16))") (class "Default")
      (node (ref "REM") (pin "2") (pinfunction "2_2") (pintype "passive"))
      (node (ref "SERIAL") (pin "4") (pinfunction "4_4") (pintype "passive"))
      (node (ref "UC1") (pin "2") (pinfunction "PD0(RXD/PCINT16)_2") (pintype "bidirectional"))
    )
    (net (code "77") (name "Net-(UC1-PD1(TXD{slash}PCINT17))") (class "Default")
      (node (ref "SERIAL") (pin "5") (pinfunction "5_5") (pintype "passive"))
      (node (ref "UC1") (pin "3") (pinfunction "PD1(TXD/PCINT17)_3") (pintype "bidirectional"))
    )
    (net (code "78") (name "unconnected-(AUDIOJACK1-Pad2)") (class "Default")
      (node (ref "AUDIOJACK1") (pin "2") (pinfunction "2_2") (pintype "passive"))
    )
    (net (code "79") (name "unconnected-(AUDIOJACK1-Pad4)") (class "Default")
      (node (ref "AUDIOJACK1") (pin "4") (pinfunction "4_4") (pintype "passive"))
    )
    (net (code "80") (name "unconnected-(AUDIOJACK1-Pad5)") (class "Default")
      (node (ref "AUDIOJACK1") (pin "5") (pinfunction "5_5") (pintype "passive"))
    )
    (net (code "81") (name "unconnected-(DRV1-OUT0-Pad28)") (class "Default")
      (node (ref "DRV1") (pin "28") (pinfunction "OUT0_28") (pintype "output"))
    )
    (net (code "82") (name "unconnected-(DRV1-OUT7-Pad7)") (class "Default")
      (node (ref "DRV1") (pin "7") (pinfunction "OUT7_7") (pintype "output"))
    )
    (net (code "83") (name "unconnected-(DRV1-OUT8-Pad8)") (class "Default")
      (node (ref "DRV1") (pin "8") (pinfunction "OUT8_8") (pintype "output"))
    )
    (net (code "84") (name "unconnected-(DRV1-OUT15-Pad15)") (class "Default")
      (node (ref "DRV1") (pin "15") (pinfunction "OUT15_15") (pintype "output"))
    )
    (net (code "85") (name "unconnected-(DRV1-XERR-Pad16)") (class "Default")
      (node (ref "DRV1") (pin "16") (pinfunction "XERR_16") (pintype "output"))
    )
    (net (code "86") (name "unconnected-(DRV2-OUT0-Pad28)") (class "Default")
      (node (ref "DRV2") (pin "28") (pinfunction "OUT0_28") (pintype "output"))
    )
    (net (code "87") (name "unconnected-(DRV2-OUT7-Pad7)") (class "Default")
      (node (ref "DRV2") (pin "7") (pinfunction "OUT7_7") (pintype "output"))
    )
    (net (code "88") (name "unconnected-(DRV2-OUT14-Pad14)") (class "Default")
      (node (ref "DRV2") (pin "14") (pinfunction "OUT14_14") (pintype "output"))
    )
    (net (code "89") (name "unconnected-(DRV2-OUT15-Pad15)") (class "Default")
      (node (ref "DRV2") (pin "15") (pinfunction "OUT15_15") (pintype "output"))
    )
    (net (code "90") (name "unconnected-(DRV2-XERR-Pad16)") (class "Default")
      (node (ref "DRV2") (pin "16") (pinfunction "XERR_16") (pintype "output"))
    )
    (net (code "91") (name "unconnected-(DRV3-OUT0-Pad28)") (class "Default")
      (node (ref "DRV3") (pin "28") (pinfunction "OUT0_28") (pintype "output"))
    )
    (net (code "92") (name "unconnected-(DRV3-OUT7-Pad7)") (class "Default")
      (node (ref "DRV3") (pin "7") (pinfunction "OUT7_7") (pintype "output"))
    )
    (net (code "93") (name "unconnected-(DRV3-OUT8-Pad8)") (class "Default")
      (node (ref "DRV3") (pin "8") (pinfunction "OUT8_8") (pintype "output"))
    )
    (net (code "94") (name "unconnected-(DRV3-OUT15-Pad15)") (class "Default")
      (node (ref "DRV3") (pin "15") (pinfunction "OUT15_15") (pintype "output"))
    )
    (net (code "95") (name "unconnected-(DRV3-SOUT-Pad17)") (class "Default")
      (node (ref "DRV3") (pin "17") (pinfunction "SOUT_17") (pintype "output"))
    )
    (net (code "96") (name "unconnected-(DRV3-XERR-Pad16)") (class "Default")
      (node (ref "DRV3") (pin "16") (pinfunction "XERR_16") (pintype "output"))
    )
    (net (code "97") (name "unconnected-(J1-Pad2)") (class "Default")
      (node (ref "J1") (pin "2") (pinfunction "2_2") (pintype "passive"))
    )
    (net (code "98") (name "unconnected-(SERIAL-Pad3)") (class "Default")
      (node (ref "SERIAL") (pin "3") (pinfunction "3_3") (pintype "passive"))
    )
    (net (code "99") (name "unconnected-(UC1-AREF-Pad21)") (class "Default")
      (node (ref "UC1") (pin "21") (pinfunction "AREF_21") (pintype "passive"))
    )
    (net (code "100") (name "unconnected-(UC1-AVCC-Pad20)") (class "Default")
      (node (ref "UC1") (pin "20") (pinfunction "AVCC_20") (pintype "passive"))
    )
    (net (code "101") (name "unconnected-(UC1-PB0(ICP1{slash}CLKO{slash}PCINT0)-Pad14)") (class "Default")
      (node (ref "UC1") (pin "14") (pinfunction "PB0(ICP1/CLKO/PCINT0)_14") (pintype "bidirectional"))
    )
    (net (code "102") (name "unconnected-(UC1-PB4(MISO{slash}PCINT4)-Pad18)") (class "Default")
      (node (ref "UC1") (pin "18") (pinfunction "PB4(MISO/PCINT4)_18") (pintype "bidirectional"))
    )
    (net (code "103") (name "unconnected-(UC1-PC0(ADC0{slash}PCINT8)-Pad23)") (class "Default")
      (node (ref "UC1") (pin "23") (pinfunction "PC0(ADC0/PCINT8)_23") (pintype "bidirectional"))
    )
    (net (code "104") (name "unconnected-(UC1-PC1(ADC1{slash}PCINT9)-Pad24)") (class "Default")
      (node (ref "UC1") (pin "24") (pinfunction "PC1(ADC1/PCINT9)_24") (pintype "bidirectional"))
    )
    (net (code "105") (name "unconnected-(UC1-PC2(ADC2{slash}PCINT10)-Pad25)") (class "Default")
      (node (ref "UC1") (pin "25") (pinfunction "PC2(ADC2/PCINT10)_25") (pintype "bidirectional"))
    )
    (net (code "106") (name "unconnected-(UC1-PC4(ADC4{slash}SDA{slash}PCINT12)-Pad27)") (class "Default")
      (node (ref "UC1") (pin "27") (pinfunction "PC4(ADC4/SDA/PCINT12)_27") (pintype "bidirectional"))
    )
    (net (code "107") (name "unconnected-(UC1-PC5(ADC5{slash}SCLPCINT13)-Pad28)") (class "Default")
      (node (ref "UC1") (pin "28") (pinfunction "PC5(ADC5/SCLPCINT13)_28") (pintype "bidirectional"))
    )
    (net (code "108") (name "unconnected-(UC1-PD2(INT0{slash}PCINT18)-Pad4)") (class "Default")
      (node (ref "UC1") (pin "4") (pinfunction "PD2(INT0/PCINT18)_4") (pintype "bidirectional"))
    )
    (net (code "109") (name "unconnected-(UC1-PD4(T0{slash}XCK{slash}PCINT20)-Pad6)") (class "Default")
      (node (ref "UC1") (pin "6") (pinfunction "PD4(T0/XCK/PCINT20)_6") (pintype "bidirectional"))
    )
    (net (code "110") (name "unconnected-(UC1-PD5(T1{slash}OC0B{slash}PCINT21)-Pad11)") (class "Default")
      (node (ref "UC1") (pin "11") (pinfunction "PD5(T1/OC0B/PCINT21)_11") (pintype "bidirectional"))
    )
    (net (code "111") (name "unconnected-(UC1-PD6(AIN0{slash}OC0A{slash}PCINT22)-Pad12)") (class "Default")
      (node (ref "UC1") (pin "12") (pinfunction "PD6(AIN0/OC0A/PCINT22)_12") (pintype "bidirectional"))
    )
    (net (code "112") (name "unconnected-(UC1-PD7(AIN1{slash}PCINT23)-Pad13)") (class "Default")
      (node (ref "UC1") (pin "13") (pinfunction "PD7(AIN1/PCINT23)_13") (pintype "bidirectional"))
    )
  )
)
